# Emitter_Driver.net
KiCad netlist of a schematic drawn in Altium Designer
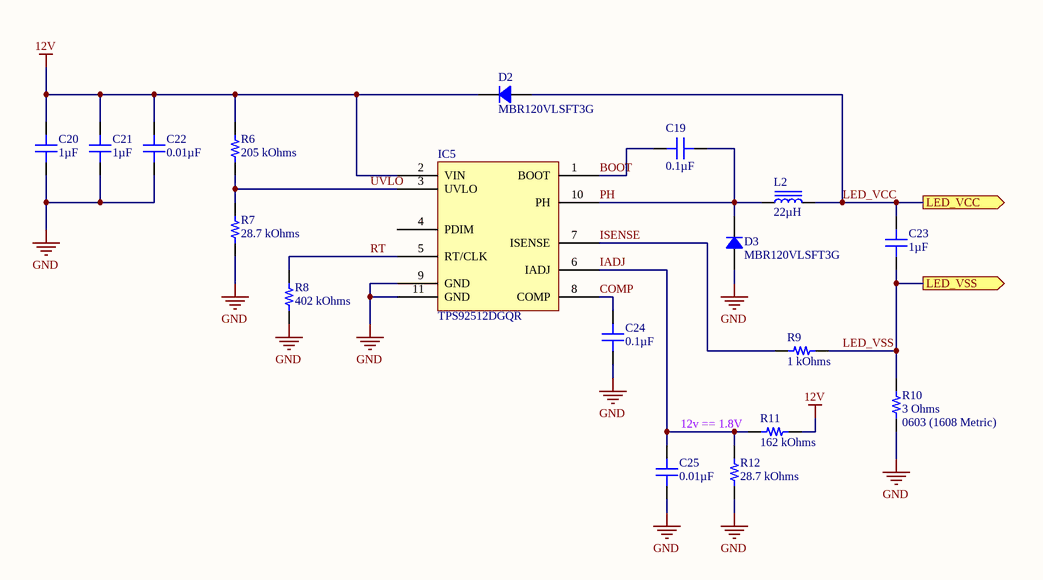
[diagram p0: Emitter Driver.SchDoc]

(export (version "E")
  (design (tool "Eeschema 10.0.6"))
  (components
    (comp (ref "C19")
      (value "0.1µF")
      (footprint "CAP 0603_1608")
      (description "CAP CER 0.1UF 25V Y5V 0603")
      (fields (field (name "PART NUMBER") "CC0603MRY5V8BB104") (field (name "MANUFACTURER") "Yageo"))
      (libsource (lib "Celestial Altium Library - altium_library") (part "Capacitor"))
    )
    (comp (ref "C20")
      (value "1µF")
      (footprint "CAP 0603_1608")
      (description "CAP CER 1UF 25V X5R 0603")
      (fields (field (name "PART NUMBER") "CC0603KRX5R8BB105") (field (name "MANUFACTURER") "Yageo"))
      (libsource (lib "Celestial Altium Library - altium_library") (part "Capacitor"))
    )
    (comp (ref "C21")
      (value "1µF")
      (footprint "CAP 0603_1608")
      (description "CAP CER 1UF 25V X5R 0603")
      (fields (field (name "PART NUMBER") "CC0603KRX5R8BB105") (field (name "MANUFACTURER") "Yageo"))
      (libsource (lib "Celestial Altium Library - altium_library") (part "Capacitor"))
    )
    (comp (ref "C22")
      (value "0.01µF")
      (footprint "CAP 0603_1608")
      (description "CAP CER 0.01UF 250V X7R 0603")
      (fields (field (name "PART NUMBER") "C0603C103KARACAUTO") (field (name "MANUFACTURER") "KEMET"))
      (libsource (lib "Celestial Altium Library - altium_library") (part "Capacitor"))
    )
    (comp (ref "C23")
      (value "1µF")
      (footprint "CAP 0603_1608")
      (description "CAP CER 1UF 25V X5R 0603")
      (fields (field (name "PART NUMBER") "CC0603KRX5R8BB105") (field (name "MANUFACTURER") "Yageo"))
      (libsource (lib "Celestial Altium Library - altium_library") (part "Capacitor"))
    )
    (comp (ref "C24")
      (value "0.1µF")
      (footprint "CAP 0603_1608")
      (description "CAP CER 0.1UF 25V Y5V 0603")
      (fields (field (name "PART NUMBER") "CC0603MRY5V8BB104") (field (name "MANUFACTURER") "Yageo"))
      (libsource (lib "Celestial Altium Library - altium_library") (part "Capacitor"))
    )
    (comp (ref "C25")
      (value "0.01µF")
      (footprint "CAP 0603_1608")
      (description "CAP CER 0.01UF 250V X7R 0603")
      (fields (field (name "PART NUMBER") "C0603C103KARACAUTO") (field (name "MANUFACTURER") "KEMET"))
      (libsource (lib "Celestial Altium Library - altium_library") (part "Capacitor"))
    )
    (comp (ref "D2")
      (value "MBR120VLSFT3G")
      (footprint "SOD123F")
      (description "DIODE SCHOTTKY 20V 1A SOD123FL")
      (fields (field (name "MANUFACTURER") "ON Semiconductor"))
      (libsource (lib "Celestial Altium Library - altium_library") (part "Diode"))
    )
    (comp (ref "D3")
      (value "MBR120VLSFT3G")
      (footprint "SOD123F")
      (description "DIODE SCHOTTKY 20V 1A SOD123FL")
      (fields (field (name "MANUFACTURER") "ON Semiconductor"))
      (libsource (lib "Celestial Altium Library - altium_library") (part "Diode"))
    )
    (comp (ref "IC5")
      (value "TPS92512DGQR")
      (footprint "TI MSOP-10 DGQ")
      (description "IC LED CNV CONST CUR 2.5A 10MSOP")
      (fields (field (name "MANUFACTURER") "Texas Instruments"))
      (libsource (lib "Celestial Altium Library - altium_library") (part "TI TPS92512HVDGQR"))
    )
    (comp (ref "L2")
      (value "22µH")
      (footprint "TDK VLCF4028-2")
      (description "FIXED IND 22UH 710MA 140 MOHM")
      (fields
        (field (name "PART NUMBER") "VLCF5028T-220MR71-2")
        (field (name "MANUFACTURER") "TDK Corporation")
      )
      (libsource (lib "Celestial Altium Library - altium_library") (part "Inductor"))
    )
    (comp (ref "R6")
      (value "205 kOhms")
      (footprint "RES 0603_1608")
      (description "RES SMD 205K OHM 1% 1/10W 0603")
      (fields
        (field (name "PART NUMBER") "ERJ-3EKF2053V")
        (field (name "MANUFACTURER") "Panasonic Electronic Components")
      )
      (libsource (lib "Celestial Altium Library - altium_library") (part "Resistor"))
    )
    (comp (ref "R7")
      (value "28.7 kOhms")
      (footprint "RES 0603_1608")
      (description "RES SMD 28.7K OHM 1% 1/10W 0603")
      (fields
        (field (name "PART NUMBER") "ERJ-3EKF2872V")
        (field (name "MANUFACTURER") "Panasonic Electronic Components")
      )
      (libsource (lib "Celestial Altium Library - altium_library") (part "Resistor"))
    )
    (comp (ref "R8")
      (value "402 kOhms")
      (footprint "RES 0603_1608")
      (description "RES SMD 402K OHM 1% 1/10W 0603")
      (fields
        (field (name "PART NUMBER") "ERJ-3EKF4023V")
        (field (name "MANUFACTURER") "Panasonic Electronic Components")
      )
      (libsource (lib "Celestial Altium Library - altium_library") (part "Resistor"))
    )
    (comp (ref "R9")
      (value "1 kOhms")
      (footprint "RES 0603_1608")
      (description "RES SMD 1K OHM 1% 1/10W 0603")
      (fields
        (field (name "PART NUMBER") "ERJ-3EKF1001V")
        (field (name "MANUFACTURER") "Panasonic Electronic Components")
      )
      (libsource (lib "Celestial Altium Library - altium_library") (part "Resistor"))
    )
    (comp (ref "R10")
      (value "3 Ohms")
      (footprint "STACKPOLE CSR0603")
      (description "RES SMD 3 OHM 1% 1/4W 0603")
      (fields
        (field (name "PART NUMBER") "ERJ-3BQF3R0V")
        (field (name "PACKAGE / CASE") "0603 (1608 Metric)")
        (field (name "MANUFACTURER") "Panasonic Electronic Components")
      )
      (libsource (lib "Celestial Altium Library - altium_library") (part "Resistor"))
    )
    (comp (ref "R11")
      (value "162 kOhms")
      (footprint "RES 0603_1608")
      (description "RES SMD 162K OHM 1% 1/10W 0603")
      (fields
        (field (name "PART NUMBER") "ERJ-3EKF1623V")
        (field (name "MANUFACTURER") "Panasonic Electronic Components")
      )
      (libsource (lib "Celestial Altium Library - altium_library") (part "Resistor"))
    )
    (comp (ref "R12")
      (value "28.7 kOhms")
      (footprint "RES 0603_1608")
      (description "RES SMD 28.7K OHM 1% 1/10W 0603")
      (fields
        (field (name "PART NUMBER") "ERJ-3EKF2872V")
        (field (name "MANUFACTURER") "Panasonic Electronic Components")
      )
      (libsource (lib "Celestial Altium Library - altium_library") (part "Resistor"))
    )
  )
  (nets
    (net (code "1") (name "/BOOT") (class "Default")
      (node (ref "C19") (pin "2") (pinfunction "2_2") (pintype "passive"))
      (node (ref "IC5") (pin "1") (pinfunction "BOOT_1") (pintype "passive"))
    )
    (net (code "2") (name "/COMP") (class "Default")
      (node (ref "C24") (pin "1") (pinfunction "1_1") (pintype "passive"))
      (node (ref "IC5") (pin "8") (pinfunction "COMP_8") (pintype "passive"))
    )
    (net (code "3") (name "/IADJ") (class "Default")
      (node (ref "C25") (pin "2") (pinfunction "2_2") (pintype "passive"))
      (node (ref "IC5") (pin "6") (pinfunction "IADJ_6") (pintype "passive"))
      (node (ref "R11") (pin "2") (pinfunction "2_2") (pintype "passive"))
      (node (ref "R12") (pin "2") (pinfunction "2_2") (pintype "passive"))
    )
    (net (code "4") (name "/ISENSE") (class "Default")
      (node (ref "IC5") (pin "7") (pinfunction "ISENSE_7") (pintype "passive"))
      (node (ref "R9") (pin "2") (pinfunction "2_2") (pintype "passive"))
    )
    (net (code "5") (name "/LED_VCC") (class "Default")
      (node (ref "C23") (pin "2") (pinfunction "2_2") (pintype "passive"))
      (node (ref "D2") (pin "1") (pinfunction "1_1") (pintype "passive"))
      (node (ref "L2") (pin "2") (pinfunction "2_2") (pintype "passive"))
    )
    (net (code "6") (name "/LED_VSS") (class "Default")
      (node (ref "C23") (pin "1") (pinfunction "1_1") (pintype "passive"))
      (node (ref "R10") (pin "2") (pinfunction "2_2") (pintype "passive"))
      (node (ref "R9") (pin "1") (pinfunction "1_1") (pintype "passive"))
    )
    (net (code "7") (name "/PH") (class "Default")
      (node (ref "C19") (pin "1") (pinfunction "1_1") (pintype "passive"))
      (node (ref "D3") (pin "2") (pinfunction "2_2") (pintype "passive"))
      (node (ref "IC5") (pin "10") (pinfunction "PH_10") (pintype "passive"))
      (node (ref "L2") (pin "1") (pinfunction "1_1") (pintype "passive"))
    )
    (net (code "8") (name "/RT") (class "Default")
      (node (ref "IC5") (pin "5") (pinfunction "RT/CLK_5") (pintype "passive"))
      (node (ref "R8") (pin "2") (pinfunction "2_2") (pintype "passive"))
    )
    (net (code "9") (name "/UVLO") (class "Default")
      (node (ref "IC5") (pin "3") (pinfunction "UVLO_3") (pintype "passive"))
      (node (ref "R6") (pin "1") (pinfunction "1_1") (pintype "passive"))
      (node (ref "R7") (pin "2") (pinfunction "2_2") (pintype "passive"))
    )
    (net (code "10") (name "12V") (class "Default")
      (node (ref "C20") (pin "2") (pinfunction "2_2") (pintype "passive"))
      (node (ref "C21") (pin "2") (pinfunction "2_2") (pintype "passive"))
      (node (ref "C22") (pin "2") (pinfunction "2_2") (pintype "passive"))
      (node (ref "D2") (pin "2") (pinfunction "2_2") (pintype "passive"))
      (node (ref "IC5") (pin "2") (pinfunction "VIN_2") (pintype "passive"))
      (node (ref "R11") (pin "1") (pinfunction "1_1") (pintype "passive"))
      (node (ref "R6") (pin "2") (pinfunction "2_2") (pintype "passive"))
    )
    (net (code "11") (name "GND") (class "Default")
      (node (ref "C20") (pin "1") (pinfunction "1_1") (pintype "passive"))
      (node (ref "C21") (pin "1") (pinfunction "1_1") (pintype "passive"))
      (node (ref "C22") (pin "1") (pinfunction "1_1") (pintype "passive"))
      (node (ref "C24") (pin "2") (pinfunction "2_2") (pintype "passive"))
      (node (ref "C25") (pin "1") (pinfunction "1_1") (pintype "passive"))
      (node (ref "D3") (pin "1") (pinfunction "1_1") (pintype "passive"))
      (node (ref "IC5") (pin "11") (pinfunction "GND_11") (pintype "passive"))
      (node (ref "IC5") (pin "9") (pinfunction "GND_9") (pintype "passive"))
      (node (ref "R10") (pin "1") (pinfunction "1_1") (pintype "passive"))
      (node (ref "R12") (pin "1") (pinfunction "1_1") (pintype "passive"))
      (node (ref "R7") (pin "1") (pinfunction "1_1") (pintype "passive"))
      (node (ref "R8") (pin "1") (pinfunction "1_1") (pintype "passive"))
    )
    (net (code "12") (name "unconnected-(IC5-PDIM-Pad4)") (class "Default")
      (node (ref "IC5") (pin "4") (pinfunction "PDIM_4") (pintype "passive"))
    )
  )
)
